# FontesLineares.net
KiCad netlist of a schematic drawn in Altium Designer
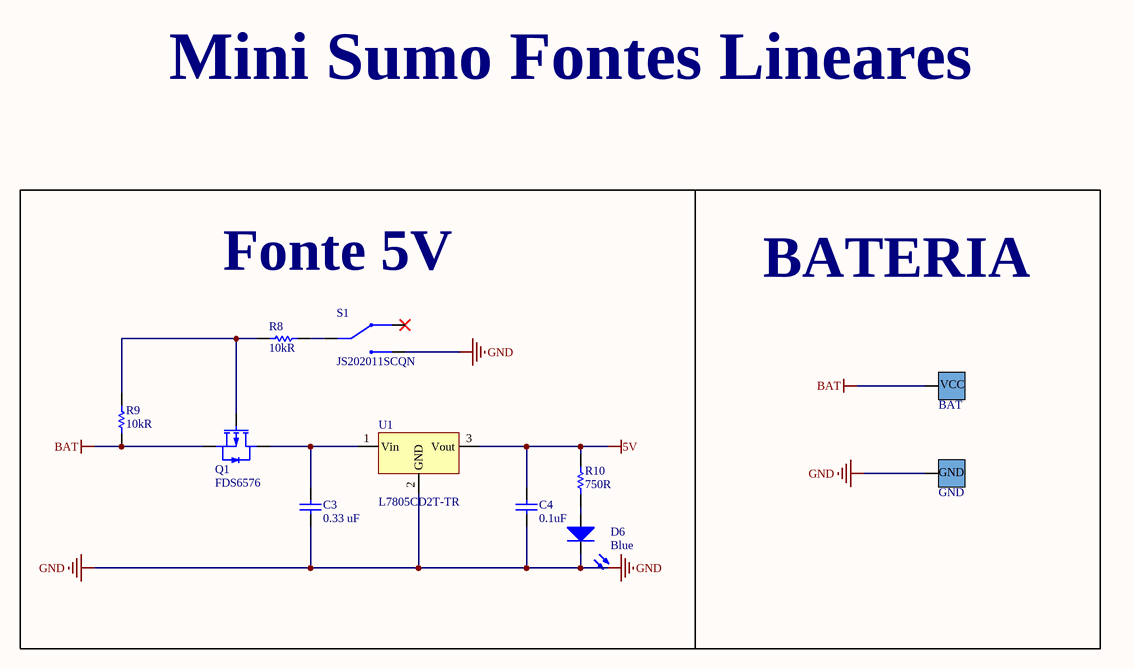
[diagram p0: FontesLineares.SchDoc]

(export (version "E")
  (design (tool "Eeschema 10.0.6"))
  (components
    (comp (ref "BAT")
      (value "Source Pad")
      (footprint "PAD_ALIMENTAÇÃO_MINI")
      (description "VCC PAD MINI SUMÔ")
      (libsource (lib "Uai!Tecas") (part "Source Pad Mini Sumô"))
    )
    (comp (ref "C3")
      (value "0.33 uF")
      (footprint "C0805")
      (description "CAP CER 0.33UF 25V X7R 0805")
      (fields
        (field (name "MANUFACTURER") "Murata Eletronics")
        (field (name "PART NUMBER") "GCM21BR71E334KA37K")
        (field (name "LIBRARY CONTROL - PERSON THAT CHECKED FOOTPRINT") "Nikaum")
        (field (name "LIBRARY CONTROL - PERSON THAT CHECKED SCHEMATIC") "Nikaum")
        (field (name "LIBRARY CONTROL - PERSON THAT DID THE LAST UPDATE FOOTPRINT") "Nikaum")
        (field (name "LIBRARY CONTROL - PERSON THAT DID THE LAST UPDATE SCHEMATIC") "Nikaum")
      )
      (libsource (lib "Uai!Tecas") (part "GCM21BR71E334KA37K"))
    )
    (comp (ref "C4")
      (value "0.1uF")
      (footprint "C0805")
      (description "CAP CER 0.1uF 25V X7R 0805")
      (fields
        (field (name "MANUFACTURER") "Kemet")
        (field (name "PART NUMBER") "C0805C104M3RACTU")
        (field (name "LIBRARY CONTROL - PERSON THAT CHECKED SCHEMATIC") "Guilherme")
        (field (name "LIBRARY CONTROL - PERSON THAT DID THE LAST UPDATE SCHEMATIC") "Marcos")
      )
      (libsource (lib "Uai!Tecas") (part "C0805C104M3RACTU"))
    )
    (comp (ref "D6")
      (value "Blue")
      (footprint "DIODO_2-SMD-3215")
      (description "LED 75mW BLUE 45MCD 3215")
      (fields
        (field (name "MANUFACTURER") "Everlight Electronics")
        (field (name "PART NUMBER") "EAST3215BA5")
        (field (name "LIBRARY CONTROL - PERSON THAT CHECKED FOOTPRINT") "Lucas")
        (field (name "LIBRARY CONTROL - PERSON THAT CHECKED SCHEMATIC") "Lucas")
        (field (name "LIBRARY CONTROL - PERSON THAT DID THE LAST UPDATE FOOTPRINT") "Stéfany (Ster)")
        (field (name "LIBRARY CONTROL - PERSON THAT DID THE LAST UPDATE SCHEMATIC") "Stéfany (Ster)")
      )
      (libsource (lib "Diodo") (part "EAST3215BA5"))
    )
    (comp (ref "GND")
      (value "Ground Pad")
      (footprint "PAD_ALIMENTAÇÃO_MINI")
      (description "GND PAD MINI SUMÔ")
      (libsource (lib "Uai!Tecas") (part "Ground Pad Mini Sumô"))
    )
    (comp (ref "Q1")
      (value "FDS6576")
      (footprint "SOIC-8")
      (description "MOSFET P-CH 20V 11A SOIC-8")
      (fields (field (name "PART NUMBER") "SOIC-8") (field (name "MANUFACTURER") "onsemi / Fairchild"))
      (libsource (lib "Uai!Tecas") (part "FDS6576"))
    )
    (comp (ref "R8")
      (value "10kR")
      (footprint "RESISTOR_0603")
      (description "RES SMD 10K OHM 5% 1/10W 0603")
      (fields
        (field (name "MANUFACTURER") "Yageo")
        (field (name "PART NUMBER") "RC0603JR-0710KL")
        (field (name "LIBRARY CONTROL - PERSON THAT CHECKED SCHEMATIC") "Marcos")
        (field (name "LIBRARY CONTROL - PERSON THAT DID THE LAST UPDATE FOOTPRINT") "Dalarme")
        (field (name "LIBRARY CONTROL - PERSON THAT DID THE LAST UPDATE SCHEMATIC") "Marcos")
      )
      (libsource (lib "Uai!Tecas") (part "RC0603JR-0710KL"))
    )
    (comp (ref "R9")
      (value "10kR")
      (footprint "RESISTOR_0603")
      (description "RES SMD 10K OHM 5% 1/10W 0603")
      (fields
        (field (name "MANUFACTURER") "Yageo")
        (field (name "PART NUMBER") "RC0603JR-0710KL")
        (field (name "LIBRARY CONTROL - PERSON THAT CHECKED SCHEMATIC") "Marcos")
        (field (name "LIBRARY CONTROL - PERSON THAT DID THE LAST UPDATE FOOTPRINT") "Dalarme")
        (field (name "LIBRARY CONTROL - PERSON THAT DID THE LAST UPDATE SCHEMATIC") "Marcos")
      )
      (libsource (lib "Uai!Tecas") (part "RC0603JR-0710KL"))
    )
    (comp (ref "R10")
      (value "750R")
      (footprint "RESISTOR_0805")
      (description "RES SMD 750 OHM 5% 1/8W 0805")
      (fields
        (field (name "MANUFACTURER") "Panasonic")
        (field (name "PART NUMBER") "ERJ-6GEYJ751V")
        (field (name "LIBRARY CONTROL - PERSON THAT CHECKED FOOTPRINT") "Nikaum")
        (field (name "LIBRARY CONTROL - PERSON THAT CHECKED SCHEMATIC") "Guilherme")
        (field (name "LIBRARY CONTROL - PERSON THAT DID THE LAST UPDATE FOOTPRINT") "Dalarme")
        (field (name "LIBRARY CONTROL - PERSON THAT DID THE LAST UPDATE SCHEMATIC") "Nikaum")
      )
      (libsource (lib "Uai!Tecas") (part "ERJ-6GEYJ751V"))
    )
    (comp (ref "S1")
      (value "JS202011SCQN")
      (footprint "DPDT")
      (description "DEEP SWITCH 4 POSITIONS")
      (fields
        (field (name "MANUFACTURER") "C&K")
        (field (name "MOUSER PART NUMBER") "611-JS202011SCQN")
        (field (name "LIBRARY CONTROL - PERSON THAT CHECKED FOOTPRINT") "Nikaum")
        (field (name "LIBRARY CONTROL - PERSON THAT CHECKED SCHEMATIC") "Nikaum")
        (field (name "LIBRARY CONTROL - PERSON THAT DID THE LAST UPDATE FOOTPRINT") "Nikaum")
        (field (name "LIBRARY CONTROL - PERSON THAT DID THE LAST UPDATE SCHEMATIC") "Nikaum")
      )
      (libsource (lib "Uai!Tecas") (part "JS202011SCQN"))
    )
    (comp (ref "U1")
      (value "L7805CD2T-TR")
      (footprint "D2PAK")
      (description "IC REG LINEAR 5V 1A D2PAK")
      (fields
        (field (name "MANUFACTURER") "ST")
        (field (name "LIBRARY CONTROL - PERSON THAT CHECKED FOOTPRINT") "Nícolas")
        (field (name "LIBRARY CONTROL - PERSON THAT CHECKED SCHEMATIC") "Nícolas")
        (field (name "LIBRARY CONTROL - PERSON THAT DID THE LAST UPDATE SCHEMATIC") "Nícolas")
      )
      (libsource (lib "Uai!Tecas") (part "L7805CD2T-TR"))
    )
  )
  (nets
    (net (code "1") (name "5V") (class "Default")
      (node (ref "C4") (pin "2") (pinfunction "2_2") (pintype "passive"))
      (node (ref "R10") (pin "2") (pinfunction "2_2") (pintype "passive"))
      (node (ref "U1") (pin "3") (pinfunction "Vout_3") (pintype "power_in"))
    )
    (net (code "2") (name "BAT") (class "Default")
      (node (ref "BAT") (pin "A") (pinfunction "VCC_A") (pintype "passive"))
      (node (ref "Q1") (pin "S") (pinfunction "S_S") (pintype "passive"))
      (node (ref "R9") (pin "1") (pinfunction "1_1") (pintype "passive"))
    )
    (net (code "3") (name "GND") (class "Default")
      (node (ref "C3") (pin "1") (pinfunction "1_1") (pintype "passive"))
      (node (ref "C4") (pin "1") (pinfunction "1_1") (pintype "passive"))
      (node (ref "D6") (pin "C") (pinfunction "C_C") (pintype "passive"))
      (node (ref "GND") (pin "A") (pinfunction "GND_A") (pintype "passive"))
      (node (ref "S1") (pin "A3") (pinfunction "3_A3") (pintype "passive"))
      (node (ref "U1") (pin "2") (pinfunction "GND_2") (pintype "power_in"))
    )
    (net (code "4") (name "Net-(D6-PadA)") (class "Default")
      (node (ref "D6") (pin "A") (pinfunction "A_A") (pintype "passive"))
      (node (ref "R10") (pin "1") (pinfunction "1_1") (pintype "passive"))
    )
    (net (code "5") (name "Net-(Q1-PadG)") (class "Default")
      (node (ref "Q1") (pin "G") (pinfunction "G_G") (pintype "passive"))
      (node (ref "R8") (pin "2") (pinfunction "2_2") (pintype "passive"))
      (node (ref "R9") (pin "2") (pinfunction "2_2") (pintype "passive"))
    )
    (net (code "6") (name "Net-(S1-1)") (class "Default")
      (node (ref "R8") (pin "1") (pinfunction "1_1") (pintype "passive"))
      (node (ref "S1") (pin "A1") (pinfunction "1_A1") (pintype "passive"))
    )
    (net (code "7") (name "Net-(U1-Vin)") (class "Default")
      (node (ref "C3") (pin "2") (pinfunction "2_2") (pintype "passive"))
      (node (ref "Q1") (pin "D") (pinfunction "D_D") (pintype "passive"))
      (node (ref "U1") (pin "1") (pinfunction "Vin_1") (pintype "power_in"))
    )
    (net (code "8") (name "unconnected-(S1-4-PadA2)") (class "Default")
      (node (ref "S1") (pin "A2") (pinfunction "4_A2") (pintype "passive+no_connect"))
    )
  )
)
